# Regulator.net
KiCad netlist of a schematic drawn in Altium Designer
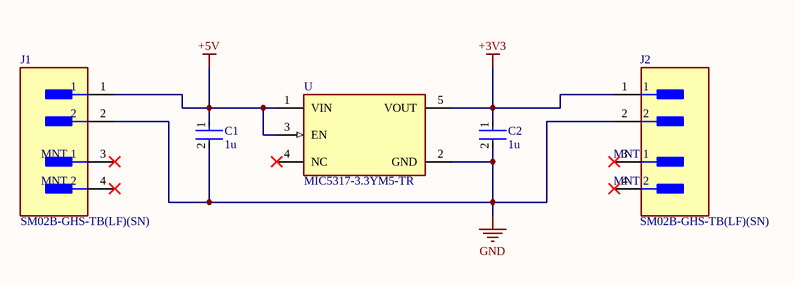
[diagram p0: Regulator.SchDoc]

(export (version "E")
  (design (tool "Eeschema 10.0.6"))
  (components
    (comp (ref "C1")
      (value "1u")
      (footprint "FP-CC0805-0_85-MFG")
      (description "CAP CER 1UF 10V X7R 0805")
      (fields
        (field (name "MANUFACTURER PART NUMBER") "CC0805MKX7R6BB105")
        (field (name "OCTOPART") "https://octopart.com/cc0805mkx7r6bb105-yageo-71334590")
      )
      (libsource (lib "Altium Content Vault") (part "11868f565c42a9108669ba33697ecf6"))
    )
    (comp (ref "C2")
      (value "1u")
      (footprint "FP-CC0805-0_85-MFG")
      (description "CAP CER 1UF 10V X7R 0805")
      (fields
        (field (name "MANUFACTURER PART NUMBER") "CC0805MKX7R6BB105")
        (field (name "OCTOPART") "https://octopart.com/cc0805mkx7r6bb105-yageo-71334590")
      )
      (libsource (lib "Altium Content Vault") (part "11868f565c42a9108669ba33697ecf6"))
    )
    (comp (ref "J1")
      (value "SM02B-GHS-TB(LF)(SN)")
      (footprint "FP-SM02B-GHS-TB_LF_SN-MFG")
      (description "CONN HEADER SMD R/A 2POS 1.25MM")
      (libsource (lib "Altium Content Vault") (part "56ec3178a87b3978bdc1b3682cd516a"))
    )
    (comp (ref "J2")
      (value "SM02B-GHS-TB(LF)(SN)")
      (footprint "FP-SM02B-GHS-TB_LF_SN-MFG")
      (description "CONN HEADER SMD R/A 2POS 1.25MM")
      (libsource (lib "") (part "56ec3178a87b3978bdc1b3682cd516a_1"))
    )
    (comp (ref "U")
      (value "MIC5317-3.3YM5-TR")
      (footprint "FP-SOT23-5LD-PL-1-MFG")
      (description "IC REG LINEAR 3.3V 150MA SOT23-5")
      (libsource (lib "Altium Content Vault") (part "0a093dae7315cdc977fd108dde87457"))
    )
  )
  (nets
    (net (code "1") (name "+3V3") (class "Default")
      (node (ref "C2") (pin "1") (pinfunction "1_1") (pintype "passive"))
      (node (ref "J2") (pin "1") (pinfunction "1_1") (pintype "passive"))
      (node (ref "U") (pin "5") (pinfunction "VOUT_5") (pintype "power_in"))
    )
    (net (code "2") (name "+5V") (class "Default")
      (node (ref "C1") (pin "1") (pinfunction "1_1") (pintype "passive"))
      (node (ref "J1") (pin "1") (pinfunction "1_1") (pintype "passive"))
      (node (ref "U") (pin "1") (pinfunction "VIN_1") (pintype "power_in"))
      (node (ref "U") (pin "3") (pinfunction "EN_3") (pintype "input"))
    )
    (net (code "3") (name "GND") (class "Default")
      (node (ref "C1") (pin "2") (pinfunction "2_2") (pintype "passive"))
      (node (ref "C2") (pin "2") (pinfunction "2_2") (pintype "passive"))
      (node (ref "J1") (pin "2") (pinfunction "2_2") (pintype "passive"))
      (node (ref "J2") (pin "2") (pinfunction "2_2") (pintype "passive"))
      (node (ref "U") (pin "2") (pinfunction "GND_2") (pintype "power_in"))
    )
    (net (code "4") (name "unconnected-(J1-MNT_1-Pad3)") (class "Default")
      (node (ref "J1") (pin "3") (pinfunction "MNT_1_3") (pintype "passive+no_connect"))
    )
    (net (code "5") (name "unconnected-(J1-MNT_2-Pad4)") (class "Default")
      (node (ref "J1") (pin "4") (pinfunction "MNT_2_4") (pintype "passive+no_connect"))
    )
    (net (code "6") (name "unconnected-(J2-MNT_1-Pad3)") (class "Default")
      (node (ref "J2") (pin "3") (pinfunction "MNT_1_3") (pintype "passive+no_connect"))
    )
    (net (code "7") (name "unconnected-(J2-MNT_2-Pad4)") (class "Default")
      (node (ref "J2") (pin "4") (pinfunction "MNT_2_4") (pintype "passive+no_connect"))
    )
    (net (code "8") (name "unconnected-(U-NC-Pad4)") (class "Default")
      (node (ref "U") (pin "4") (pinfunction "NC_4") (pintype "passive+no_connect"))
    )
  )
)
